# PowerBoard.net
KiCad netlist of a schematic drawn in EAGLE
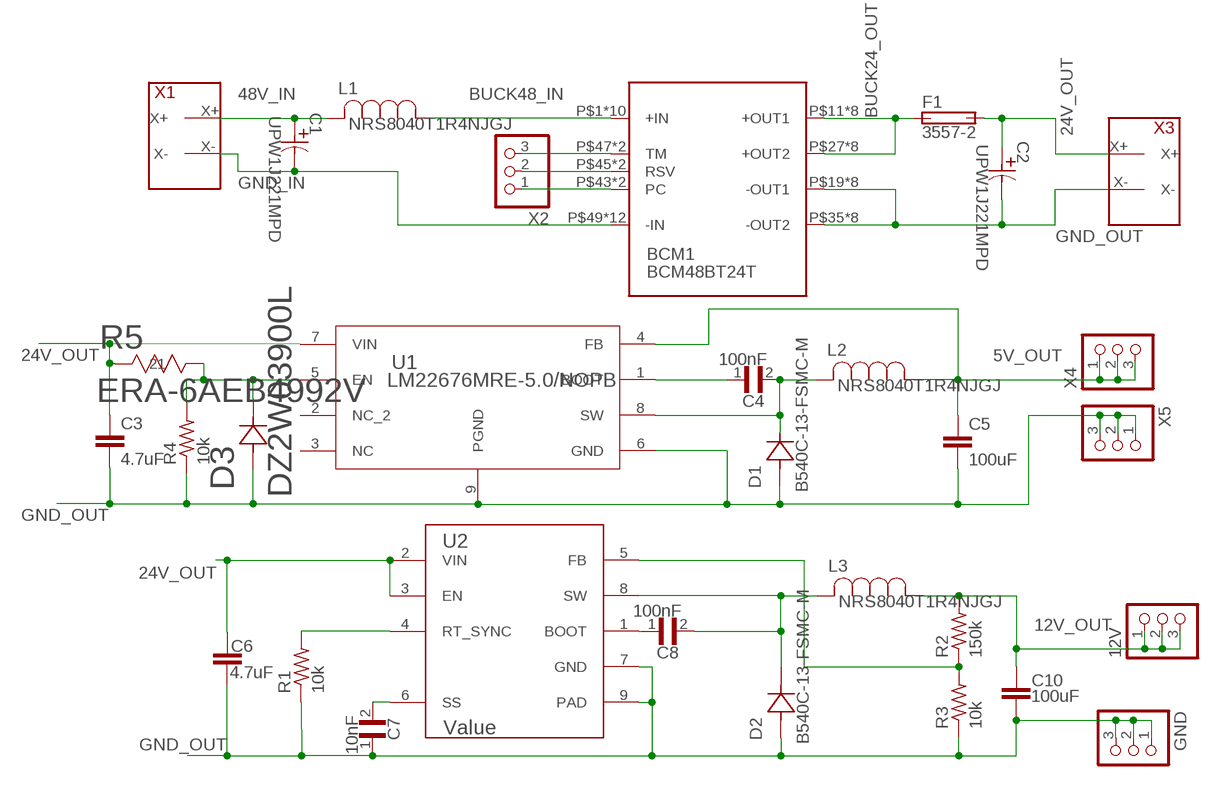
[diagram p0: schematic, sheet 1]

(export (version "E")
  (design (tool "Eeschema 10.0.6"))
  (components
    (comp (ref "12V")
      (value "9-146281-0")
      (footprint "eagle-import:TE_9-146281-0")
      (fields (field (name "MF") "TE Connectivity"))
      (libsource (lib "eagle-import") (part "9-146281-0"))
    )
    (comp (ref "BCM1")
      (value "BCM48BT24T")
      (footprint "eagle-import:BCM48BT24T")
      (libsource (lib "eagle-import") (part "BCM48BT24T"))
    )
    (comp (ref "C1")
      (value "UPW1J221MPD")
      (footprint "eagle-import:PCAP_10X20-THRU-ELECT")
      (libsource (lib "eagle-import") (part "UPW1J221MPD"))
    )
    (comp (ref "C2")
      (value "UPW1J221MPD")
      (footprint "eagle-import:PCAP_10X20-THRU-ELECT")
      (libsource (lib "eagle-import") (part "UPW1J221MPD"))
    )
    (comp (ref "C3")
      (value "4.7uF")
      (footprint "eagle-import:0603")
      (libsource (lib "eagle-import") (part "4.7UF0603"))
    )
    (comp (ref "C4")
      (value "100nF")
      (footprint "eagle-import:CAPC2012X135N")
      (fields (field (name "MF") "Murata Electronics") (field (name "MP") "GRM21BR60E107ME15L"))
      (libsource (lib "eagle-import") (part "GRM21BR60E107ME15L"))
    )
    (comp (ref "C5")
      (value "100uF")
      (footprint "eagle-import:1210")
      (libsource (lib "eagle-import") (part "10UF-1210-50V-20%"))
    )
    (comp (ref "C6")
      (value "4.7uF")
      (footprint "eagle-import:0603")
      (libsource (lib "eagle-import") (part "4.7UF0603"))
    )
    (comp (ref "C7")
      (value "10nF")
      (footprint "eagle-import:CAPC2012X135N")
      (fields (field (name "MF") "Murata Electronics") (field (name "MP") "GRM21BR60E107ME15L"))
      (libsource (lib "eagle-import") (part "GRM21BR60E107ME15L"))
    )
    (comp (ref "C8")
      (value "100nF")
      (footprint "eagle-import:CAPC2012X135N")
      (fields (field (name "MF") "Murata Electronics") (field (name "MP") "GRM21BR60E107ME15L"))
      (libsource (lib "eagle-import") (part "GRM21BR60E107ME15L"))
    )
    (comp (ref "C10")
      (value "100uF")
      (footprint "eagle-import:1210")
      (libsource (lib "eagle-import") (part "10UF-1210-50V-20%"))
    )
    (comp (ref "D1")
      (value "B540C-13-FSMC-M")
      (footprint "eagle-import:SMC-M")
      (fields (field (name "MANUFACTURER_PART_NUMBER") "B540C13F"))
      (libsource (lib "eagle-import") (part "B540C-13-FSMC-M"))
    )
    (comp (ref "D2")
      (value "B540C-13-FSMC-M")
      (footprint "eagle-import:SMC-M")
      (fields (field (name "MANUFACTURER_PART_NUMBER") "B540C13F"))
      (libsource (lib "eagle-import") (part "B540C-13-FSMC-M"))
    )
    (comp (ref "D3")
      (value "DZ2W03900L")
      (footprint "eagle-import:MINI2-F3-B")
      (libsource (lib "eagle-import") (part "DZ2W03900L"))
    )
    (comp (ref "F1")
      (value "3557-2")
      (footprint "eagle-import:FUSE_3557-2")
      (fields (field (name "MF") "Keystone"))
      (libsource (lib "eagle-import") (part "3557-2"))
    )
    (comp (ref "GND")
      (value "9-146281-0")
      (footprint "eagle-import:TE_9-146281-0")
      (fields (field (name "MF") "TE Connectivity"))
      (libsource (lib "eagle-import") (part "9-146281-0"))
    )
    (comp (ref "L1")
      (value "NRS8040T1R4NJGJ")
      (footprint "eagle-import:IND_TAIYO_NRS8040")
      (libsource (lib "eagle-import") (part "NRS8040T1R4NJGJ"))
    )
    (comp (ref "L2")
      (value "NRS8040T1R4NJGJ")
      (footprint "eagle-import:IND_TAIYO_NRS8040")
      (libsource (lib "eagle-import") (part "NRS8040T1R4NJGJ"))
    )
    (comp (ref "L3")
      (value "NRS8040T1R4NJGJ")
      (footprint "eagle-import:IND_TAIYO_NRS8040")
      (libsource (lib "eagle-import") (part "NRS8040T1R4NJGJ"))
    )
    (comp (ref "R1")
      (value "10k")
      (footprint "eagle-import:R0603")
      (libsource (lib "eagle-import") (part "R-US_R0603"))
    )
    (comp (ref "R2")
      (value "150k")
      (footprint "eagle-import:R0603")
      (libsource (lib "eagle-import") (part "R-US_R0603"))
    )
    (comp (ref "R3")
      (value "10k")
      (footprint "eagle-import:R0603")
      (libsource (lib "eagle-import") (part "R-US_R0603"))
    )
    (comp (ref "R4")
      (value "10k")
      (footprint "eagle-import:R0603")
      (libsource (lib "eagle-import") (part "R-US_R0603"))
    )
    (comp (ref "R5")
      (value "ERA-6AEB4992V")
      (footprint "eagle-import:RES_ERA6A_0805")
      (fields (field (name "MANUFACTURER_PART_NUMBER") "ERA6AEB4992V"))
      (libsource (lib "eagle-import") (part "ERA-6AEB4992V"))
    )
    (comp (ref "U1")
      (value "LM22676MRE-5.0/NOPB")
      (footprint "eagle-import:MRA08B")
      (fields (field (name "MANUFACTURER_PART_NUMBER") "LM22676MRE5.0NOPB"))
      (libsource (lib "eagle-import") (part "LM22676MRE-5.0/NOPB"))
    )
    (comp (ref "U2")
      (value "Value")
      (footprint "eagle-import:DDA0008E_N")
      (fields
        (field (name "MANUFACTURER") "Texas Instruments")
        (field (name "MANUFACTURER_PART_NUMBER") "LMR14050SDDAR")
      )
      (libsource (lib "eagle-import") (part "LMR14050SDDAR"))
    )
    (comp (ref "X1")
      (value "XT60")
      (footprint "eagle-import:XT60")
      (libsource (lib "eagle-import") (part "XT60_XT60"))
    )
    (comp (ref "X2")
      (value "9-146281-0")
      (footprint "eagle-import:TE_9-146281-0")
      (fields (field (name "MF") "TE Connectivity"))
      (libsource (lib "eagle-import") (part "9-146281-0"))
    )
    (comp (ref "X3")
      (value "XT60")
      (footprint "eagle-import:XT60")
      (libsource (lib "eagle-import") (part "XT60_XT60"))
    )
    (comp (ref "X4")
      (value "9-146281-0")
      (footprint "eagle-import:TE_9-146281-0")
      (fields (field (name "MF") "TE Connectivity"))
      (libsource (lib "eagle-import") (part "9-146281-0"))
    )
    (comp (ref "X5")
      (value "9-146281-0")
      (footprint "eagle-import:TE_9-146281-0")
      (fields (field (name "MF") "TE Connectivity"))
      (libsource (lib "eagle-import") (part "9-146281-0"))
    )
  )
  (nets
    (net (code "1") (name "/5V_OUT") (class "Default")
      (node (ref "C5") (pin "1") (pinfunction "1_1") (pintype "passive"))
      (node (ref "L2") (pin "1") (pinfunction "1_1") (pintype "passive"))
      (node (ref "U1") (pin "4") (pinfunction "FB_4") (pintype "input"))
      (node (ref "X4") (pin "1") (pinfunction "1_1") (pintype "passive"))
      (node (ref "X4") (pin "2") (pinfunction "2_2") (pintype "passive"))
      (node (ref "X4") (pin "3") (pinfunction "3_3") (pintype "passive"))
    )
    (net (code "2") (name "/12V_OUT") (class "Default")
      (node (ref "12V") (pin "1") (pinfunction "1_1") (pintype "passive"))
      (node (ref "12V") (pin "2") (pinfunction "2_2") (pintype "passive"))
      (node (ref "12V") (pin "3") (pinfunction "3_3") (pintype "passive"))
      (node (ref "C10") (pin "1") (pinfunction "1_1") (pintype "passive"))
      (node (ref "L3") (pin "1") (pinfunction "1_1") (pintype "passive"))
      (node (ref "R2") (pin "2") (pinfunction "2_2") (pintype "passive"))
    )
    (net (code "3") (name "/24V_OUT") (class "Default")
      (node (ref "C2") (pin "1") (pinfunction "11_1") (pintype "passive"))
      (node (ref "C3") (pin "1") (pinfunction "1_1") (pintype "passive"))
      (node (ref "C6") (pin "1") (pinfunction "1_1") (pintype "passive"))
      (node (ref "F1") (pin "3") (pinfunction "2A_3") (pintype "passive"))
      (node (ref "F1") (pin "4") (pinfunction "2A_4") (pintype "passive"))
      (node (ref "R5") (pin "2") (pinfunction "21_2") (pintype "passive"))
      (node (ref "U1") (pin "7") (pinfunction "VIN_7") (pintype "power_in"))
      (node (ref "U2") (pin "2") (pinfunction "VIN_2") (pintype "power_in"))
      (node (ref "U2") (pin "3") (pinfunction "EN_3") (pintype "input"))
      (node (ref "X3") (pin "X+") (pinfunction "X+_X+") (pintype "bidirectional"))
    )
    (net (code "4") (name "/48V_IN") (class "Default")
      (node (ref "C1") (pin "1") (pinfunction "11_1") (pintype "passive"))
      (node (ref "L1") (pin "2") (pinfunction "2_2") (pintype "passive"))
      (node (ref "X1") (pin "X+") (pinfunction "X+_X+") (pintype "bidirectional"))
    )
    (net (code "5") (name "/BUCK24_OUT") (class "Default")
      (node (ref "BCM1") (pin "P$11") (pinfunction "+OUT1_P$11") (pintype "output"))
      (node (ref "BCM1") (pin "P$12") (pinfunction "+OUT1_P$12") (pintype "output"))
      (node (ref "BCM1") (pin "P$13") (pinfunction "+OUT1_P$13") (pintype "output"))
      (node (ref "BCM1") (pin "P$14") (pinfunction "+OUT1_P$14") (pintype "output"))
      (node (ref "BCM1") (pin "P$15") (pinfunction "+OUT1_P$15") (pintype "output"))
      (node (ref "BCM1") (pin "P$16") (pinfunction "+OUT1_P$16") (pintype "output"))
      (node (ref "BCM1") (pin "P$17") (pinfunction "+OUT1_P$17") (pintype "output"))
      (node (ref "BCM1") (pin "P$18") (pinfunction "+OUT1_P$18") (pintype "output"))
      (node (ref "BCM1") (pin "P$27") (pinfunction "+OUT2_P$27") (pintype "output"))
      (node (ref "BCM1") (pin "P$28") (pinfunction "+OUT2_P$28") (pintype "output"))
      (node (ref "BCM1") (pin "P$29") (pinfunction "+OUT2_P$29") (pintype "output"))
      (node (ref "BCM1") (pin "P$30") (pinfunction "+OUT2_P$30") (pintype "output"))
      (node (ref "BCM1") (pin "P$31") (pinfunction "+OUT2_P$31") (pintype "output"))
      (node (ref "BCM1") (pin "P$32") (pinfunction "+OUT2_P$32") (pintype "output"))
      (node (ref "BCM1") (pin "P$33") (pinfunction "+OUT2_P$33") (pintype "output"))
      (node (ref "BCM1") (pin "P$34") (pinfunction "+OUT2_P$34") (pintype "output"))
      (node (ref "F1") (pin "1") (pinfunction "1A_1") (pintype "passive"))
      (node (ref "F1") (pin "2") (pinfunction "1A_2") (pintype "passive"))
    )
    (net (code "6") (name "/BUCK48_IN") (class "Default")
      (node (ref "BCM1") (pin "P$1") (pinfunction "+IN_P$1") (pintype "input"))
      (node (ref "BCM1") (pin "P$10") (pinfunction "+IN_P$10") (pintype "input"))
      (node (ref "BCM1") (pin "P$2") (pinfunction "+IN_P$2") (pintype "input"))
      (node (ref "BCM1") (pin "P$3") (pinfunction "+IN_P$3") (pintype "input"))
      (node (ref "BCM1") (pin "P$4") (pinfunction "+IN_P$4") (pintype "input"))
      (node (ref "BCM1") (pin "P$5") (pinfunction "+IN_P$5") (pintype "input"))
      (node (ref "BCM1") (pin "P$6") (pinfunction "+IN_P$6") (pintype "input"))
      (node (ref "BCM1") (pin "P$7") (pinfunction "+IN_P$7") (pintype "input"))
      (node (ref "BCM1") (pin "P$8") (pinfunction "+IN_P$8") (pintype "input"))
      (node (ref "BCM1") (pin "P$9") (pinfunction "+IN_P$9") (pintype "input"))
      (node (ref "L1") (pin "1") (pinfunction "1_1") (pintype "passive"))
    )
    (net (code "7") (name "/GND_IN") (class "Default")
      (node (ref "BCM1") (pin "P$49") (pinfunction "-IN_P$49") (pintype "input"))
      (node (ref "BCM1") (pin "P$50") (pinfunction "-IN_P$50") (pintype "input"))
      (node (ref "BCM1") (pin "P$51") (pinfunction "-IN_P$51") (pintype "input"))
      (node (ref "BCM1") (pin "P$52") (pinfunction "-IN_P$52") (pintype "input"))
      (node (ref "BCM1") (pin "P$53") (pinfunction "-IN_P$53") (pintype "input"))
      (node (ref "BCM1") (pin "P$54") (pinfunction "-IN_P$54") (pintype "input"))
      (node (ref "BCM1") (pin "P$55") (pinfunction "-IN_P$55") (pintype "input"))
      (node (ref "BCM1") (pin "P$56") (pinfunction "-IN_P$56") (pintype "input"))
      (node (ref "BCM1") (pin "P$57") (pinfunction "-IN_P$57") (pintype "input"))
      (node (ref "BCM1") (pin "P$58") (pinfunction "-IN_P$58") (pintype "input"))
      (node (ref "BCM1") (pin "P$59") (pinfunction "-IN_P$59") (pintype "input"))
      (node (ref "BCM1") (pin "P$60") (pinfunction "-IN_P$60") (pintype "input"))
      (node (ref "C1") (pin "2") (pinfunction "22_2") (pintype "passive"))
      (node (ref "X1") (pin "X-") (pinfunction "X-_X-") (pintype "bidirectional"))
    )
    (net (code "8") (name "/GND_OUT") (class "Default")
      (node (ref "BCM1") (pin "P$19") (pinfunction "-OUT1_P$19") (pintype "output"))
      (node (ref "BCM1") (pin "P$20") (pinfunction "-OUT1_P$20") (pintype "output"))
      (node (ref "BCM1") (pin "P$21") (pinfunction "-OUT1_P$21") (pintype "output"))
      (node (ref "BCM1") (pin "P$22") (pinfunction "-OUT1_P$22") (pintype "output"))
      (node (ref "BCM1") (pin "P$23") (pinfunction "-OUT1_P$23") (pintype "output"))
      (node (ref "BCM1") (pin "P$24") (pinfunction "-OUT1_P$24") (pintype "output"))
      (node (ref "BCM1") (pin "P$25") (pinfunction "-OUT1_P$25") (pintype "output"))
      (node (ref "BCM1") (pin "P$26") (pinfunction "-OUT1_P$26") (pintype "output"))
      (node (ref "BCM1") (pin "P$35") (pinfunction "-OUT2_P$35") (pintype "output"))
      (node (ref "BCM1") (pin "P$36") (pinfunction "-OUT2_P$36") (pintype "output"))
      (node (ref "BCM1") (pin "P$37") (pinfunction "-OUT2_P$37") (pintype "output"))
      (node (ref "BCM1") (pin "P$38") (pinfunction "-OUT2_P$38") (pintype "output"))
      (node (ref "BCM1") (pin "P$39") (pinfunction "-OUT2_P$39") (pintype "output"))
      (node (ref "BCM1") (pin "P$40") (pinfunction "-OUT2_P$40") (pintype "output"))
      (node (ref "BCM1") (pin "P$41") (pinfunction "-OUT2_P$41") (pintype "output"))
      (node (ref "BCM1") (pin "P$42") (pinfunction "-OUT2_P$42") (pintype "output"))
      (node (ref "C10") (pin "2") (pinfunction "2_2") (pintype "passive"))
      (node (ref "C2") (pin "2") (pinfunction "22_2") (pintype "passive"))
      (node (ref "C3") (pin "2") (pinfunction "2_2") (pintype "passive"))
      (node (ref "C5") (pin "2") (pinfunction "2_2") (pintype "passive"))
      (node (ref "C6") (pin "2") (pinfunction "2_2") (pintype "passive"))
      (node (ref "C7") (pin "1") (pinfunction "1_1") (pintype "passive"))
      (node (ref "D1") (pin "2") (pinfunction "21_2") (pintype "passive"))
      (node (ref "D2") (pin "2") (pinfunction "21_2") (pintype "passive"))
      (node (ref "D3") (pin "2") (pinfunction "22_2") (pintype "passive"))
      (node (ref "GND") (pin "1") (pinfunction "1_1") (pintype "passive"))
      (node (ref "GND") (pin "2") (pinfunction "2_2") (pintype "passive"))
      (node (ref "GND") (pin "3") (pinfunction "3_3") (pintype "passive"))
      (node (ref "R1") (pin "1") (pinfunction "1_1") (pintype "passive"))
      (node (ref "R3") (pin "1") (pinfunction "1_1") (pintype "passive"))
      (node (ref "R4") (pin "1") (pinfunction "1_1") (pintype "passive"))
      (node (ref "U1") (pin "6") (pinfunction "GND_6") (pintype "power_in"))
      (node (ref "U1") (pin "9") (pinfunction "PGND_9") (pintype "power_in"))
      (node (ref "U2") (pin "7") (pinfunction "GND_7") (pintype "power_in"))
      (node (ref "U2") (pin "9") (pinfunction "PAD_9") (pintype "power_in"))
      (node (ref "X3") (pin "X-") (pinfunction "X-_X-") (pintype "bidirectional"))
      (node (ref "X5") (pin "1") (pinfunction "1_1") (pintype "passive"))
      (node (ref "X5") (pin "2") (pinfunction "2_2") (pintype "passive"))
      (node (ref "X5") (pin "3") (pinfunction "3_3") (pintype "passive"))
    )
    (net (code "9") (name "Net-(BCM1-PC-PadP$43)") (class "Default")
      (node (ref "BCM1") (pin "P$43") (pinfunction "PC_P$43") (pintype "bidirectional"))
      (node (ref "BCM1") (pin "P$44") (pinfunction "PC_P$44") (pintype "bidirectional"))
      (node (ref "X2") (pin "1") (pinfunction "1_1") (pintype "passive"))
    )
    (net (code "10") (name "Net-(BCM1-RSV-PadP$45)") (class "Default")
      (node (ref "BCM1") (pin "P$45") (pinfunction "RSV_P$45") (pintype "bidirectional"))
      (node (ref "BCM1") (pin "P$46") (pinfunction "RSV_P$46") (pintype "bidirectional"))
      (node (ref "X2") (pin "2") (pinfunction "2_2") (pintype "passive"))
    )
    (net (code "11") (name "Net-(BCM1-TM-PadP$47)") (class "Default")
      (node (ref "BCM1") (pin "P$47") (pinfunction "TM_P$47") (pintype "bidirectional"))
      (node (ref "BCM1") (pin "P$48") (pinfunction "TM_P$48") (pintype "bidirectional"))
      (node (ref "X2") (pin "3") (pinfunction "3_3") (pintype "passive"))
    )
    (net (code "12") (name "Net-(D1-12)") (class "Default")
      (node (ref "C4") (pin "2") (pinfunction "2_2") (pintype "passive"))
      (node (ref "D1") (pin "1") (pinfunction "12_1") (pintype "passive"))
      (node (ref "L2") (pin "2") (pinfunction "2_2") (pintype "passive"))
      (node (ref "U1") (pin "8") (pinfunction "SW_8") (pintype "power_in"))
    )
    (net (code "13") (name "Net-(D2-12)") (class "Default")
      (node (ref "C8") (pin "2") (pinfunction "2_2") (pintype "passive"))
      (node (ref "D2") (pin "1") (pinfunction "12_1") (pintype "passive"))
      (node (ref "L3") (pin "2") (pinfunction "2_2") (pintype "passive"))
      (node (ref "U2") (pin "8") (pinfunction "SW_8") (pintype "power_in"))
    )
    (net (code "14") (name "Net-(D3-11)") (class "Default")
      (node (ref "D3") (pin "1") (pinfunction "11_1") (pintype "passive"))
      (node (ref "R4") (pin "2") (pinfunction "2_2") (pintype "passive"))
      (node (ref "R5") (pin "1") (pinfunction "12_1") (pintype "passive"))
      (node (ref "U1") (pin "5") (pinfunction "EN_5") (pintype "input"))
    )
    (net (code "15") (name "Net-(U1-BOOT)") (class "Default")
      (node (ref "C4") (pin "1") (pinfunction "1_1") (pintype "passive"))
      (node (ref "U1") (pin "1") (pinfunction "BOOT_1") (pintype "passive"))
    )
    (net (code "16") (name "Net-(U2-BOOT)") (class "Default")
      (node (ref "C8") (pin "1") (pinfunction "1_1") (pintype "passive"))
      (node (ref "U2") (pin "1") (pinfunction "BOOT_1") (pintype "passive"))
    )
    (net (code "17") (name "Net-(U2-FB)") (class "Default")
      (node (ref "R2") (pin "1") (pinfunction "1_1") (pintype "passive"))
      (node (ref "R3") (pin "2") (pinfunction "2_2") (pintype "passive"))
      (node (ref "U2") (pin "5") (pinfunction "FB_5") (pintype "input"))
    )
    (net (code "18") (name "Net-(U2-RT_SYNC)") (class "Default")
      (node (ref "R1") (pin "2") (pinfunction "2_2") (pintype "passive"))
      (node (ref "U2") (pin "4") (pinfunction "RT_SYNC_4") (pintype "passive"))
    )
    (net (code "19") (name "Net-(U2-SS)") (class "Default")
      (node (ref "C7") (pin "2") (pinfunction "2_2") (pintype "passive"))
      (node (ref "U2") (pin "6") (pinfunction "SS_6") (pintype "input"))
    )
    (net (code "20") (name "unconnected-(U1-NC-Pad3)") (class "Default")
      (node (ref "U1") (pin "3") (pinfunction "NC_3") (pintype "passive"))
    )
    (net (code "21") (name "unconnected-(U1-NC_2-Pad2)") (class "Default")
      (node (ref "U1") (pin "2") (pinfunction "NC_2_2") (pintype "passive"))
    )
  )
)
